# USB-UART.net
KiCad netlist of a schematic drawn in Altium Designer
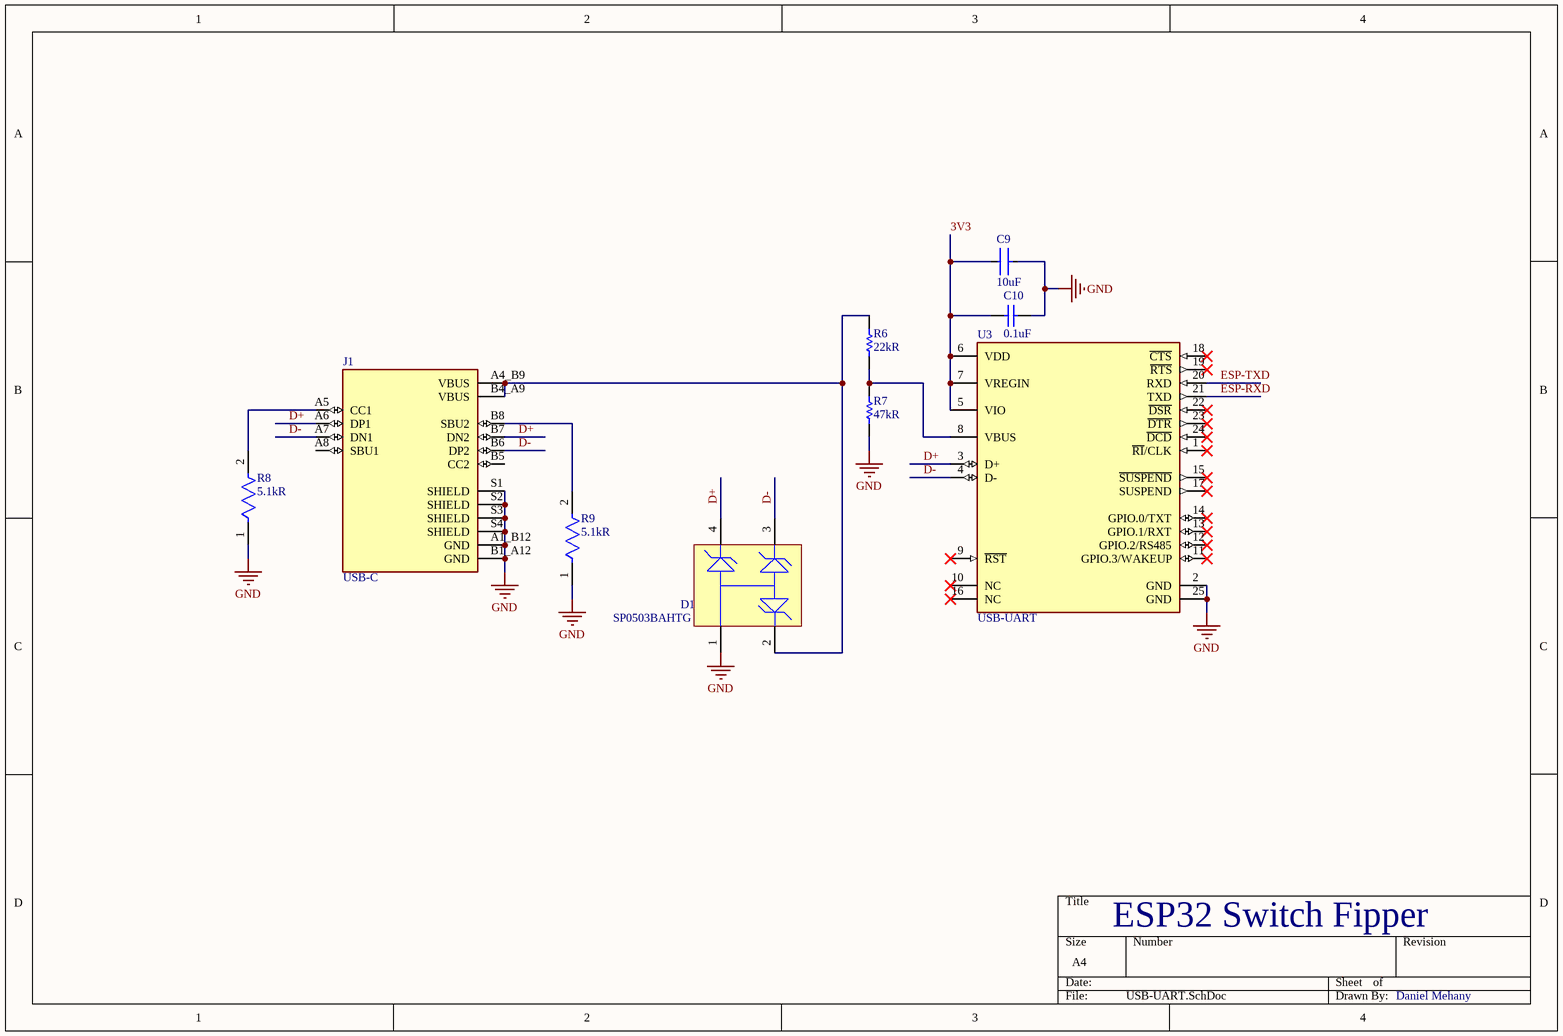
[diagram p0: USB-UART.SchDoc]

(export (version "E")
  (design (tool "Eeschema 10.0.6"))
  (components
    (comp (ref "C9")
      (value "10uF")
      (footprint "FP-CL31-IPC_C")
      (description "CAP CER 10UF 50V X5R 1206")
      (fields (field (name "TOLERANCE") "10%") (field (name "MANUFACTURER") "Samsung"))
      (libsource (lib "Altium Content Vault") (part "11868f565c42a9108669ba33697ecf6"))
    )
    (comp (ref "C10")
      (value "CL05B104KO5NNNC")
      (footprint "CAPC1050X55X23ML05T13")
      (description "Chip Capacitor, 100 nF, +/- 10%, 16 V, -55 to 125 degC, 0402 (1005 Metric), RoHS, Tape and Reel")
      (fields
        (field (name "MANUFACTURER") "Samsung Electro-Mechanics")
        (field (name "CAP") "0.1uF")
        (field (name "JLCPCB PART #") "C1525")
      )
      (libsource (lib "Altium Content Vault") (part "CAP-NP-2"))
    )
    (comp (ref "D1")
      (value "SP0503BAHTG")
      (footprint "LFUS-SOT143-4_V")
      (description "TVS Diode Array, 30 pF, 30 KV, -40 to 85 degC, 4-Pin SOT143, RoHS, Tape and Reel")
      (fields (field (name "MANUFACTURER") "Littelfuse") (field (name "JLCPCB PART #") "C7074"))
      (libsource (lib "Altium Content Vault") (part "LFUS-SP0503BAHTG-SOT143-4"))
    )
    (comp (ref "J1")
      (value "USB-C")
      (footprint "HRO_TYPE-C-31-M-12")
      (description "USB Connectors 24 Receptacle 1 8.94*7.3mm RoHS\r\nTYPE-C-31-M-12")
      (fields (field (name "MF") "HRO Electronics Co., Ltd.") (field (name "MP") "TYPE-C-31-M-12"))
      (libsource (lib "TYPE-C-31-M-12") (part "TYPE-C-31-M-12"))
    )
    (comp (ref "R6")
      (value "22kR")
      (footprint "RESC2013X70X40ML20T20")
      (description "Chip Resistor, 1 KOhm, +/- 1%, 0.125 W, -55 to 155 degC, 0805 (2012 Metric), RoHS, Tape and Reel")
      (fields (field (name "MANUFACTURER") "Panasonic") (field (name "JLCPCB PART #") "C17560"))
      (libsource (lib "Altium Content Vault") (part "RES-2"))
    )
    (comp (ref "R7")
      (value "47kR")
      (footprint "RESC2013X60X40NL15T20")
      (fields
        (field (name "PART NUMBER") "CRCW080510K0FKEAHP")
        (field (name "MANUFACTURER") "Vishay Dale")
        (field (name "JLCPCB PART #") "C17713")
      )
      (libsource (lib "Altium Content Vault") (part "RES"))
    )
    (comp (ref "R8")
      (value "5.1kR")
      (footprint "FP-ERJ3EK-MFG")
      (description "RES SMD 5.1K OHM 1% 1/10W 0603")
      (fields (field (name "TOLERANCE") "1%") (field (name "JLCPCB PART #") "C23186"))
      (libsource (lib "Altium Content Vault") (part "1029c3af85768c4190bb7ad29bc67b5"))
    )
    (comp (ref "R9")
      (value "5.1kR")
      (footprint "FP-ERJ3EK-MFG")
      (description "RES SMD 5.1K OHM 1% 1/10W 0603")
      (fields (field (name "TOLERANCE") "1%") (field (name "JLCPCB PART #") "C23186"))
      (libsource (lib "Altium Content Vault") (part "1029c3af85768c4190bb7ad29bc67b5"))
    )
    (comp (ref "U3")
      (value "USB-UART")
      (footprint "FP-CP2102N-A02-GQFN24R-MFG")
      (description "IC USB TO UART BRIDGE QFN24\r\nCP2102N-A02-GQFN24R")
      (fields (field (name "JLCPCB PART #") "C969151"))
      (libsource (lib "Altium Content Vault") (part "83e8975dde71cc570f99d23b4d888c9"))
    )
  )
  (nets
    (net (code "1") (name "/3V3") (class "Default")
      (node (ref "C10") (pin "2") (pinfunction "2_2") (pintype "passive"))
      (node (ref "C9") (pin "2") (pinfunction "2_2") (pintype "passive"))
      (node (ref "U3") (pin "5") (pinfunction "VIO_5") (pintype "power_in"))
      (node (ref "U3") (pin "6") (pinfunction "VDD_6") (pintype "power_in"))
      (node (ref "U3") (pin "7") (pinfunction "VREGIN_7") (pintype "power_in"))
    )
    (net (code "2") (name "/D+") (class "Default")
      (node (ref "D1") (pin "4") (pinfunction "4_4") (pintype "passive"))
      (node (ref "J1") (pin "A6") (pinfunction "DP1_A6") (pintype "bidirectional"))
      (node (ref "J1") (pin "B7") (pinfunction "DN2_B7") (pintype "bidirectional"))
      (node (ref "U3") (pin "3") (pinfunction "D+_3") (pintype "bidirectional"))
    )
    (net (code "3") (name "/D-") (class "Default")
      (node (ref "D1") (pin "3") (pinfunction "3_3") (pintype "passive"))
      (node (ref "J1") (pin "A7") (pinfunction "DN1_A7") (pintype "bidirectional"))
      (node (ref "J1") (pin "B6") (pinfunction "DP2_B6") (pintype "bidirectional"))
      (node (ref "U3") (pin "4") (pinfunction "D-_4") (pintype "bidirectional"))
    )
    (net (code "4") (name "/ESP-RXD") (class "Default")
      (node (ref "U3") (pin "21") (pinfunction "TXD_21") (pintype "output"))
    )
    (net (code "5") (name "/ESP-TXD") (class "Default")
      (node (ref "U3") (pin "20") (pinfunction "RXD_20") (pintype "input"))
    )
    (net (code "6") (name "GND") (class "Default")
      (node (ref "C10") (pin "1") (pinfunction "1_1") (pintype "passive"))
      (node (ref "C9") (pin "1") (pinfunction "1_1") (pintype "passive"))
      (node (ref "D1") (pin "1") (pinfunction "1_1") (pintype "passive"))
      (node (ref "J1") (pin "A1_B12") (pinfunction "GND_A1_B12") (pintype "power_in"))
      (node (ref "J1") (pin "B1_A12") (pinfunction "GND_B1_A12") (pintype "power_in"))
      (node (ref "J1") (pin "S1") (pinfunction "SHIELD_S1") (pintype "passive"))
      (node (ref "J1") (pin "S2") (pinfunction "SHIELD_S2") (pintype "passive"))
      (node (ref "J1") (pin "S3") (pinfunction "SHIELD_S3") (pintype "passive"))
      (node (ref "J1") (pin "S4") (pinfunction "SHIELD_S4") (pintype "passive"))
      (node (ref "R7") (pin "1") (pinfunction "1_1") (pintype "passive"))
      (node (ref "R8") (pin "1") (pinfunction "1_1") (pintype "passive"))
      (node (ref "R9") (pin "1") (pinfunction "1_1") (pintype "passive"))
      (node (ref "U3") (pin "2") (pinfunction "GND_2") (pintype "power_in"))
      (node (ref "U3") (pin "25") (pinfunction "GND_25") (pintype "power_in"))
    )
    (net (code "7") (name "Net-(D1-Pad2)") (class "Default")
      (node (ref "D1") (pin "2") (pinfunction "2_2") (pintype "passive"))
      (node (ref "J1") (pin "A4_B9") (pinfunction "VBUS_A4_B9") (pintype "power_in"))
      (node (ref "J1") (pin "B4_A9") (pinfunction "VBUS_B4_A9") (pintype "power_in"))
      (node (ref "R6") (pin "2") (pinfunction "2_2") (pintype "passive"))
    )
    (net (code "8") (name "Net-(J1-CC1)") (class "Default")
      (node (ref "J1") (pin "A5") (pinfunction "CC1_A5") (pintype "bidirectional"))
      (node (ref "R8") (pin "2") (pinfunction "2_2") (pintype "passive"))
    )
    (net (code "9") (name "Net-(J1-SBU2)") (class "Default")
      (node (ref "J1") (pin "B8") (pinfunction "SBU2_B8") (pintype "bidirectional"))
      (node (ref "R9") (pin "2") (pinfunction "2_2") (pintype "passive"))
    )
    (net (code "10") (name "Net-(U3-VBUS)") (class "Default")
      (node (ref "R6") (pin "1") (pinfunction "1_1") (pintype "passive"))
      (node (ref "R7") (pin "2") (pinfunction "2_2") (pintype "passive"))
      (node (ref "U3") (pin "8") (pinfunction "VBUS_8") (pintype "power_in"))
    )
    (net (code "11") (name "unconnected-(J1-CC2-PadB5)") (class "Default")
      (node (ref "J1") (pin "B5") (pinfunction "CC2_B5") (pintype "bidirectional"))
    )
    (net (code "12") (name "unconnected-(J1-SBU1-PadA8)") (class "Default")
      (node (ref "J1") (pin "A8") (pinfunction "SBU1_A8") (pintype "bidirectional"))
    )
    (net (code "13") (name "unconnected-(U3-GPIO.0{slash}TXT-Pad14)") (class "Default")
      (node (ref "U3") (pin "14") (pinfunction "GPIO.0/TXT_14") (pintype "bidirectional+no_connect"))
    )
    (net (code "14") (name "unconnected-(U3-GPIO.1{slash}RXT-Pad13)") (class "Default")
      (node (ref "U3") (pin "13") (pinfunction "GPIO.1/RXT_13") (pintype "bidirectional+no_connect"))
    )
    (net (code "15") (name "unconnected-(U3-GPIO.2{slash}RS485-Pad12)") (class "Default")
      (node (ref "U3") (pin "12") (pinfunction "GPIO.2/RS485_12") (pintype "bidirectional+no_connect"))
    )
    (net (code "16") (name "unconnected-(U3-GPIO.3{slash}WAKEUP-Pad11)") (class "Default")
      (node (ref "U3") (pin "11") (pinfunction "GPIO.3/WAKEUP_11") (pintype "bidirectional+no_connect"))
    )
    (net (code "17") (name "unconnected-(U3-NC-Pad10)") (class "Default")
      (node (ref "U3") (pin "10") (pinfunction "NC_10") (pintype "passive+no_connect"))
    )
    (net (code "18") (name "unconnected-(U3-NC-Pad16)") (class "Default")
      (node (ref "U3") (pin "16") (pinfunction "NC_16") (pintype "passive+no_connect"))
    )
    (net (code "19") (name "unconnected-(U3-SUSPEND-Pad17)") (class "Default")
      (node (ref "U3") (pin "17") (pinfunction "SUSPEND_17") (pintype "output+no_connect"))
    )
    (net (code "20") (name "unconnected-(U3-~{CTS}-Pad18)") (class "Default")
      (node (ref "U3") (pin "18") (pinfunction "~{CTS}_18") (pintype "input+no_connect"))
    )
    (net (code "21") (name "unconnected-(U3-~{DCD}-Pad24)") (class "Default")
      (node (ref "U3") (pin "24") (pinfunction "~{DCD}_24") (pintype "input+no_connect"))
    )
    (net (code "22") (name "unconnected-(U3-~{DSR}-Pad22)") (class "Default")
      (node (ref "U3") (pin "22") (pinfunction "~{DSR}_22") (pintype "input+no_connect"))
    )
    (net (code "23") (name "unconnected-(U3-~{DTR}-Pad23)") (class "Default")
      (node (ref "U3") (pin "23") (pinfunction "~{DTR}_23") (pintype "output+no_connect"))
    )
    (net (code "24") (name "unconnected-(U3-~{RI}{slash}CLK-Pad1)") (class "Default")
      (node (ref "U3") (pin "1") (pinfunction "~{RI}/CLK_1") (pintype "input+no_connect"))
    )
    (net (code "25") (name "unconnected-(U3-~{RST}-Pad9)") (class "Default")
      (node (ref "U3") (pin "9") (pinfunction "~{RST}_9") (pintype "input+no_connect"))
    )
    (net (code "26") (name "unconnected-(U3-~{RTS}-Pad19)") (class "Default")
      (node (ref "U3") (pin "19") (pinfunction "~{RTS}_19") (pintype "output+no_connect"))
    )
    (net (code "27") (name "unconnected-(U3-~{SUSPEND}-Pad15)") (class "Default")
      (node (ref "U3") (pin "15") (pinfunction "~{SUSPEND}_15") (pintype "output+no_connect"))
    )
  )
)
